# FPGA_Banks_64_65_HR.net
KiCad netlist of a schematic drawn in Altium Designer
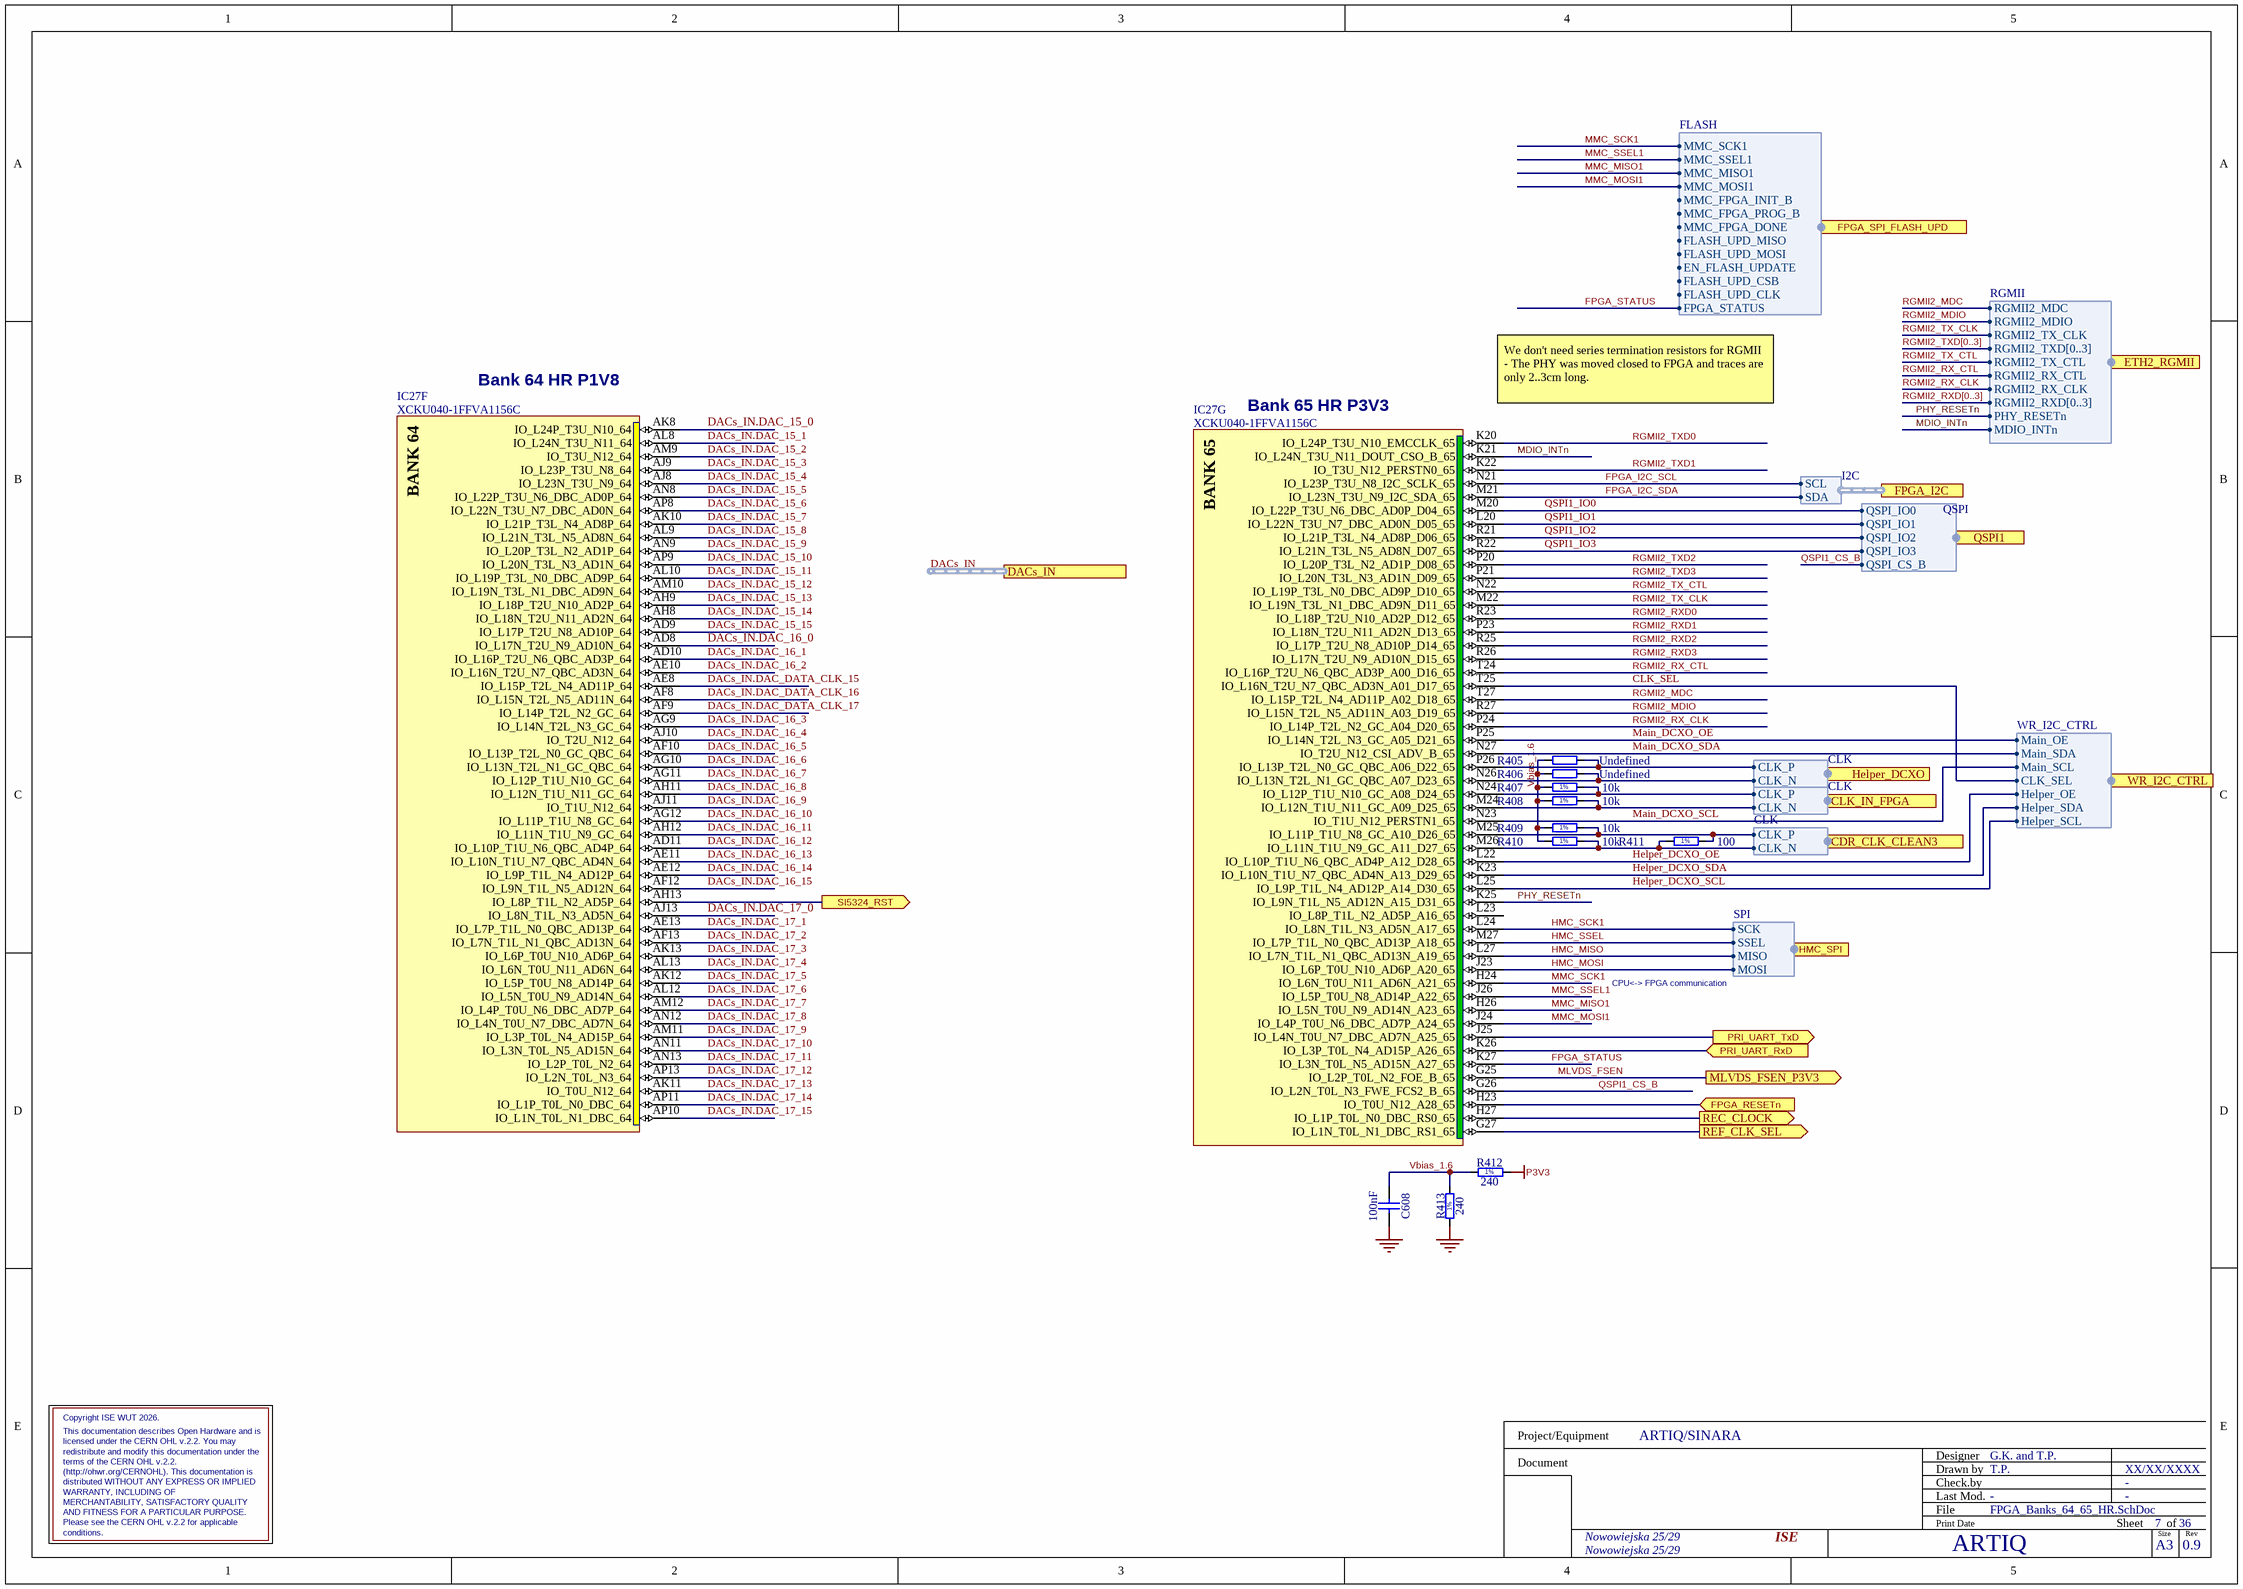
[diagram p0: FPGA_Banks_64_65_HR.SchDoc]

(export (version "E")
  (design (tool "Eeschema 10.0.6"))
  (components
    (comp (ref "C608")
      (value "100nF")
      (footprint "CAPC0603X33N")
      (description "Non-polarised capacitor")
      (fields
        (field (name "PART NUMBER") "CC0201_100NF_6.3V_10%_X5R")
        (field (name "VOLTAGE") "6.3V")
        (field (name "AUTHOR") "CERN DEM JLC")
      )
      (libsource (lib "Capacitors") (part "Capacitor - non polarized"))
    )
    (comp (ref "IC27")
      (value "XCKU040-1FFVA1156C")
      (footprint "BGA1156C100P34X34_3500X3500X350")
      (description "Kintex UltraScale FPGA, 520 I/O, 530K Cells, 1156-Ball BGA, Speed Grade 1, Commercial Grade")
      (fields (field (name "MANUFACTURER") "XILINX") (field (name "AUTHOR") "CERN DEM CA"))
      (libsource (lib "ICs And Semiconductors") (part "XCKU040-1FFVA1156C"))
    )
    (comp (ref "R405")
      (value "Undefined")
      (footprint "RESC1005X40N")
      (description "Resistor")
      (fields (field (name "PART NUMBER") "R0402_NO-VALUE") (field (name "AUTHOR") "CERN DEM JLC"))
      (libsource (lib "Resistors") (part "Resistor"))
    )
    (comp (ref "R406")
      (value "Undefined")
      (footprint "RESC1005X40N")
      (description "Resistor")
      (fields (field (name "PART NUMBER") "R0402_NO-VALUE") (field (name "AUTHOR") "CERN DEM JLC"))
      (libsource (lib "Resistors") (part "Resistor"))
    )
    (comp (ref "R407")
      (value "10k")
      (footprint "RESC1005X40N")
      (description "Resistor - 1%")
      (fields
        (field (name "PART NUMBER") "R0402_10K_1%_0.0625W_100PPM")
        (field (name "POWER") "0.0625W")
        (field (name "AUTHOR") "CERN DEM JLC")
      )
      (libsource (lib "Resistors") (part "Resistor - 1%"))
    )
    (comp (ref "R408")
      (value "10k")
      (footprint "RESC1005X40N")
      (description "Resistor - 1%")
      (fields
        (field (name "PART NUMBER") "R0402_10K_1%_0.0625W_100PPM")
        (field (name "POWER") "0.0625W")
        (field (name "AUTHOR") "CERN DEM JLC")
      )
      (libsource (lib "Resistors") (part "Resistor - 1%"))
    )
    (comp (ref "R409")
      (value "10k")
      (footprint "RESC1005X40N")
      (description "Resistor - 1%")
      (fields
        (field (name "PART NUMBER") "R0402_10K_1%_0.0625W_100PPM")
        (field (name "POWER") "0.0625W")
        (field (name "AUTHOR") "CERN DEM JLC")
      )
      (libsource (lib "Resistors") (part "Resistor - 1%"))
    )
    (comp (ref "R410")
      (value "10k")
      (footprint "RESC1005X40N")
      (description "Resistor - 1%")
      (fields
        (field (name "PART NUMBER") "R0402_10K_1%_0.0625W_100PPM")
        (field (name "POWER") "0.0625W")
        (field (name "AUTHOR") "CERN DEM JLC")
      )
      (libsource (lib "Resistors") (part "Resistor - 1%"))
    )
    (comp (ref "R411")
      (value "100")
      (footprint "RESC1005X40N")
      (description "Resistor - 1%")
      (fields
        (field (name "PART NUMBER") "R0402_100R_1%_0.0625W_100PPM")
        (field (name "POWER") "0.0625W")
        (field (name "AUTHOR") "CERN DEM JLC")
      )
      (libsource (lib "Resistors") (part "Resistor - 1%"))
    )
    (comp (ref "R412")
      (value "240")
      (footprint "RESC1005X40N")
      (description "Resistor - 1%")
      (fields
        (field (name "PART NUMBER") "R0402_240R_1%_0.0625W_100PPM")
        (field (name "POWER") "0.0625W")
        (field (name "AUTHOR") "CERN DEM JLC")
      )
      (libsource (lib "Resistors") (part "Resistor - 1%"))
    )
    (comp (ref "R413")
      (value "240")
      (footprint "RESC1005X40N")
      (description "Resistor - 1%")
      (fields
        (field (name "PART NUMBER") "R0402_240R_1%_0.0625W_100PPM")
        (field (name "POWER") "0.0625W")
        (field (name "AUTHOR") "CERN DEM JLC")
      )
      (libsource (lib "Resistors") (part "Resistor - 1%"))
    )
  )
  (nets
    (net (code "10") (name "/CLK_SEL") (class "Default")
      (node (ref "IC27") (pin "T25") (pinfunction "IO_L16N_T2U_N7_QBC_AD3N_A01_D17_65_T25") (pintype "bidirectional"))
    )
    (net (code "11") (name "/DACs_IN.DAC_15_0") (class "Default")
      (node (ref "IC27") (pin "AK8") (pinfunction "IO_L24P_T3U_N10_64_AK8") (pintype "bidirectional"))
    )
    (net (code "12") (name "/DACs_IN.DAC_15_1") (class "Default")
      (node (ref "IC27") (pin "AL8") (pinfunction "IO_L24N_T3U_N11_64_AL8") (pintype "bidirectional"))
    )
    (net (code "13") (name "/DACs_IN.DAC_15_2") (class "Default")
      (node (ref "IC27") (pin "AM9") (pinfunction "IO_T3U_N12_64_AM9") (pintype "bidirectional"))
    )
    (net (code "14") (name "/DACs_IN.DAC_15_3") (class "Default")
      (node (ref "IC27") (pin "AJ9") (pinfunction "IO_L23P_T3U_N8_64_AJ9") (pintype "bidirectional"))
    )
    (net (code "15") (name "/DACs_IN.DAC_15_4") (class "Default")
      (node (ref "IC27") (pin "AJ8") (pinfunction "IO_L23N_T3U_N9_64_AJ8") (pintype "bidirectional"))
    )
    (net (code "16") (name "/DACs_IN.DAC_15_5") (class "Default")
      (node (ref "IC27") (pin "AN8") (pinfunction "IO_L22P_T3U_N6_DBC_AD0P_64_AN8") (pintype "bidirectional"))
    )
    (net (code "17") (name "/DACs_IN.DAC_15_6") (class "Default")
      (node (ref "IC27") (pin "AP8") (pinfunction "IO_L22N_T3U_N7_DBC_AD0N_64_AP8") (pintype "bidirectional"))
    )
    (net (code "18") (name "/DACs_IN.DAC_15_7") (class "Default")
      (node (ref "IC27") (pin "AK10") (pinfunction "IO_L21P_T3L_N4_AD8P_64_AK10") (pintype "bidirectional"))
    )
    (net (code "19") (name "/DACs_IN.DAC_15_8") (class "Default")
      (node (ref "IC27") (pin "AL9") (pinfunction "IO_L21N_T3L_N5_AD8N_64_AL9") (pintype "bidirectional"))
    )
    (net (code "20") (name "/DACs_IN.DAC_15_9") (class "Default")
      (node (ref "IC27") (pin "AN9") (pinfunction "IO_L20P_T3L_N2_AD1P_64_AN9") (pintype "bidirectional"))
    )
    (net (code "21") (name "/DACs_IN.DAC_15_10") (class "Default")
      (node (ref "IC27") (pin "AP9") (pinfunction "IO_L20N_T3L_N3_AD1N_64_AP9") (pintype "bidirectional"))
    )
    (net (code "22") (name "/DACs_IN.DAC_15_11") (class "Default")
      (node (ref "IC27") (pin "AL10") (pinfunction "IO_L19P_T3L_N0_DBC_AD9P_64_AL10") (pintype "bidirectional"))
    )
    (net (code "23") (name "/DACs_IN.DAC_15_12") (class "Default")
      (node (ref "IC27") (pin "AM10") (pinfunction "IO_L19N_T3L_N1_DBC_AD9N_64_AM10") (pintype "bidirectional"))
    )
    (net (code "24") (name "/DACs_IN.DAC_15_13") (class "Default")
      (node (ref "IC27") (pin "AH9") (pinfunction "IO_L18P_T2U_N10_AD2P_64_AH9") (pintype "bidirectional"))
    )
    (net (code "25") (name "/DACs_IN.DAC_15_14") (class "Default")
      (node (ref "IC27") (pin "AH8") (pinfunction "IO_L18N_T2U_N11_AD2N_64_AH8") (pintype "bidirectional"))
    )
    (net (code "26") (name "/DACs_IN.DAC_15_15") (class "Default")
      (node (ref "IC27") (pin "AD9") (pinfunction "IO_L17P_T2U_N8_AD10P_64_AD9") (pintype "bidirectional"))
    )
    (net (code "27") (name "/DACs_IN.DAC_16_0") (class "Default")
      (node (ref "IC27") (pin "AD8") (pinfunction "IO_L17N_T2U_N9_AD10N_64_AD8") (pintype "bidirectional"))
    )
    (net (code "28") (name "/DACs_IN.DAC_16_1") (class "Default")
      (node (ref "IC27") (pin "AD10") (pinfunction "IO_L16P_T2U_N6_QBC_AD3P_64_AD10") (pintype "bidirectional"))
    )
    (net (code "29") (name "/DACs_IN.DAC_16_2") (class "Default")
      (node (ref "IC27") (pin "AE10") (pinfunction "IO_L16N_T2U_N7_QBC_AD3N_64_AE10") (pintype "bidirectional"))
    )
    (net (code "30") (name "/DACs_IN.DAC_16_3") (class "Default")
      (node (ref "IC27") (pin "AG9") (pinfunction "IO_L14N_T2L_N3_GC_64_AG9") (pintype "bidirectional"))
    )
    (net (code "31") (name "/DACs_IN.DAC_16_4") (class "Default")
      (node (ref "IC27") (pin "AJ10") (pinfunction "IO_T2U_N12_64_AJ10") (pintype "bidirectional"))
    )
    (net (code "32") (name "/DACs_IN.DAC_16_5") (class "Default")
      (node (ref "IC27") (pin "AF10") (pinfunction "IO_L13P_T2L_N0_GC_QBC_64_AF10") (pintype "bidirectional"))
    )
    (net (code "33") (name "/DACs_IN.DAC_16_6") (class "Default")
      (node (ref "IC27") (pin "AG10") (pinfunction "IO_L13N_T2L_N1_GC_QBC_64_AG10") (pintype "bidirectional"))
    )
    (net (code "34") (name "/DACs_IN.DAC_16_7") (class "Default")
      (node (ref "IC27") (pin "AG11") (pinfunction "IO_L12P_T1U_N10_GC_64_AG11") (pintype "bidirectional"))
    )
    (net (code "35") (name "/DACs_IN.DAC_16_8") (class "Default")
      (node (ref "IC27") (pin "AH11") (pinfunction "IO_L12N_T1U_N11_GC_64_AH11") (pintype "bidirectional"))
    )
    (net (code "36") (name "/DACs_IN.DAC_16_9") (class "Default")
      (node (ref "IC27") (pin "AJ11") (pinfunction "IO_T1U_N12_64_AJ11") (pintype "bidirectional"))
    )
    (net (code "37") (name "/DACs_IN.DAC_16_10") (class "Default")
      (node (ref "IC27") (pin "AG12") (pinfunction "IO_L11P_T1U_N8_GC_64_AG12") (pintype "bidirectional"))
    )
    (net (code "38") (name "/DACs_IN.DAC_16_11") (class "Default")
      (node (ref "IC27") (pin "AH12") (pinfunction "IO_L11N_T1U_N9_GC_64_AH12") (pintype "bidirectional"))
    )
    (net (code "39") (name "/DACs_IN.DAC_16_12") (class "Default")
      (node (ref "IC27") (pin "AD11") (pinfunction "IO_L10P_T1U_N6_QBC_AD4P_64_AD11") (pintype "bidirectional"))
    )
    (net (code "40") (name "/DACs_IN.DAC_16_13") (class "Default")
      (node (ref "IC27") (pin "AE11") (pinfunction "IO_L10N_T1U_N7_QBC_AD4N_64_AE11") (pintype "bidirectional"))
    )
    (net (code "41") (name "/DACs_IN.DAC_16_14") (class "Default")
      (node (ref "IC27") (pin "AE12") (pinfunction "IO_L9P_T1L_N4_AD12P_64_AE12") (pintype "bidirectional"))
    )
    (net (code "42") (name "/DACs_IN.DAC_16_15") (class "Default")
      (node (ref "IC27") (pin "AF12") (pinfunction "IO_L9N_T1L_N5_AD12N_64_AF12") (pintype "bidirectional"))
    )
    (net (code "43") (name "/DACs_IN.DAC_17_0") (class "Default")
      (node (ref "IC27") (pin "AJ13") (pinfunction "IO_L8N_T1L_N3_AD5N_64_AJ13") (pintype "bidirectional"))
    )
    (net (code "44") (name "/DACs_IN.DAC_17_1") (class "Default")
      (node (ref "IC27") (pin "AE13") (pinfunction "IO_L7P_T1L_N0_QBC_AD13P_64_AE13") (pintype "bidirectional"))
    )
    (net (code "45") (name "/DACs_IN.DAC_17_2") (class "Default")
      (node (ref "IC27") (pin "AF13") (pinfunction "IO_L7N_T1L_N1_QBC_AD13N_64_AF13") (pintype "bidirectional"))
    )
    (net (code "46") (name "/DACs_IN.DAC_17_3") (class "Default")
      (node (ref "IC27") (pin "AK13") (pinfunction "IO_L6P_T0U_N10_AD6P_64_AK13") (pintype "bidirectional"))
    )
    (net (code "47") (name "/DACs_IN.DAC_17_4") (class "Default")
      (node (ref "IC27") (pin "AL13") (pinfunction "IO_L6N_T0U_N11_AD6N_64_AL13") (pintype "bidirectional"))
    )
    (net (code "48") (name "/DACs_IN.DAC_17_5") (class "Default")
      (node (ref "IC27") (pin "AK12") (pinfunction "IO_L5P_T0U_N8_AD14P_64_AK12") (pintype "bidirectional"))
    )
    (net (code "49") (name "/DACs_IN.DAC_17_6") (class "Default")
      (node (ref "IC27") (pin "AL12") (pinfunction "IO_L5N_T0U_N9_AD14N_64_AL12") (pintype "bidirectional"))
    )
    (net (code "50") (name "/DACs_IN.DAC_17_7") (class "Default")
      (node (ref "IC27") (pin "AM12") (pinfunction "IO_L4P_T0U_N6_DBC_AD7P_64_AM12") (pintype "bidirectional"))
    )
    (net (code "51") (name "/DACs_IN.DAC_17_8") (class "Default")
      (node (ref "IC27") (pin "AN12") (pinfunction "IO_L4N_T0U_N7_DBC_AD7N_64_AN12") (pintype "bidirectional"))
    )
    (net (code "52") (name "/DACs_IN.DAC_17_9") (class "Default")
      (node (ref "IC27") (pin "AM11") (pinfunction "IO_L3P_T0L_N4_AD15P_64_AM11") (pintype "bidirectional"))
    )
    (net (code "53") (name "/DACs_IN.DAC_17_10") (class "Default")
      (node (ref "IC27") (pin "AN11") (pinfunction "IO_L3N_T0L_N5_AD15N_64_AN11") (pintype "bidirectional"))
    )
    (net (code "54") (name "/DACs_IN.DAC_17_11") (class "Default")
      (node (ref "IC27") (pin "AN13") (pinfunction "IO_L2P_T0L_N2_64_AN13") (pintype "bidirectional"))
    )
    (net (code "55") (name "/DACs_IN.DAC_17_12") (class "Default")
      (node (ref "IC27") (pin "AP13") (pinfunction "IO_L2N_T0L_N3_64_AP13") (pintype "bidirectional"))
    )
    (net (code "56") (name "/DACs_IN.DAC_17_13") (class "Default")
      (node (ref "IC27") (pin "AK11") (pinfunction "IO_T0U_N12_64_AK11") (pintype "bidirectional"))
    )
    (net (code "57") (name "/DACs_IN.DAC_17_14") (class "Default")
      (node (ref "IC27") (pin "AP11") (pinfunction "IO_L1P_T0L_N0_DBC_64_AP11") (pintype "bidirectional"))
    )
    (net (code "58") (name "/DACs_IN.DAC_17_15") (class "Default")
      (node (ref "IC27") (pin "AP10") (pinfunction "IO_L1N_T0L_N1_DBC_64_AP10") (pintype "bidirectional"))
    )
    (net (code "59") (name "/DACs_IN.DAC_DATA_CLK_15") (class "Default")
      (node (ref "IC27") (pin "AE8") (pinfunction "IO_L15P_T2L_N4_AD11P_64_AE8") (pintype "bidirectional"))
    )
    (net (code "60") (name "/DACs_IN.DAC_DATA_CLK_16") (class "Default")
      (node (ref "IC27") (pin "AF8") (pinfunction "IO_L15N_T2L_N5_AD11N_64_AF8") (pintype "bidirectional"))
    )
    (net (code "61") (name "/DACs_IN.DAC_DATA_CLK_17") (class "Default")
      (node (ref "IC27") (pin "AF9") (pinfunction "IO_L14P_T2L_N2_GC_64_AF9") (pintype "bidirectional"))
    )
    (net (code "63") (name "/FPGA_I2C_SCL") (class "Default")
      (node (ref "IC27") (pin "N21") (pinfunction "IO_L23P_T3U_N8_I2C_SCLK_65_N21") (pintype "bidirectional"))
    )
    (net (code "64") (name "/FPGA_I2C_SDA") (class "Default")
      (node (ref "IC27") (pin "M21") (pinfunction "IO_L23N_T3U_N9_I2C_SDA_65_M21") (pintype "bidirectional"))
    )
    (net (code "65") (name "/FPGA_RESETn") (class "Default")
      (node (ref "IC27") (pin "H23") (pinfunction "IO_T0U_N12_A28_65_H23") (pintype "bidirectional"))
    )
    (net (code "66") (name "/FPGA_STATUS") (class "Default")
      (node (ref "IC27") (pin "K27") (pinfunction "IO_L3N_T0L_N5_AD15N_A27_65_K27") (pintype "bidirectional"))
    )
    (net (code "67") (name "/HMC_MISO") (class "Default")
      (node (ref "IC27") (pin "L27") (pinfunction "IO_L7N_T1L_N1_QBC_AD13N_A19_65_L27") (pintype "bidirectional"))
    )
    (net (code "68") (name "/HMC_MOSI") (class "Default")
      (node (ref "IC27") (pin "J23") (pinfunction "IO_L6P_T0U_N10_AD6P_A20_65_J23") (pintype "bidirectional"))
    )
    (net (code "69") (name "/HMC_SCK1") (class "Default")
      (node (ref "IC27") (pin "L24") (pinfunction "IO_L8N_T1L_N3_AD5N_A17_65_L24") (pintype "bidirectional"))
    )
    (net (code "70") (name "/HMC_SSEL") (class "Default")
      (node (ref "IC27") (pin "M27") (pinfunction "IO_L7P_T1L_N0_QBC_AD13P_A18_65_M27") (pintype "bidirectional"))
    )
    (net (code "71") (name "/Helper_DCXO_OE") (class "Default")
      (node (ref "IC27") (pin "L22") (pinfunction "IO_L10P_T1U_N6_QBC_AD4P_A12_D28_65_L22") (pintype "bidirectional"))
    )
    (net (code "72") (name "/Helper_DCXO_SCL") (class "Default")
      (node (ref "IC27") (pin "L25") (pinfunction "IO_L9P_T1L_N4_AD12P_A14_D30_65_L25") (pintype "bidirectional"))
    )
    (net (code "73") (name "/Helper_DCXO_SDA") (class "Default")
      (node (ref "IC27") (pin "K23") (pinfunction "IO_L10N_T1U_N7_QBC_AD4N_A13_D29_65_K23") (pintype "bidirectional"))
    )
    (net (code "75") (name "/MDIO_INTn") (class "Default")
      (node (ref "IC27") (pin "K21") (pinfunction "IO_L24N_T3U_N11_DOUT_CSO_B_65_K21") (pintype "bidirectional"))
    )
    (net (code "76") (name "/MLVDS_FSEN") (class "Default")
      (node (ref "IC27") (pin "G25") (pinfunction "IO_L2P_T0L_N2_FOE_B_65_G25") (pintype "bidirectional"))
    )
    (net (code "77") (name "/MMC_MISO1") (class "Default")
      (node (ref "IC27") (pin "H26") (pinfunction "IO_L5N_T0U_N9_AD14N_A23_65_H26") (pintype "bidirectional"))
    )
    (net (code "78") (name "/MMC_MOSI1") (class "Default")
      (node (ref "IC27") (pin "J24") (pinfunction "IO_L4P_T0U_N6_DBC_AD7P_A24_65_J24") (pintype "bidirectional"))
    )
    (net (code "79") (name "/MMC_SCK1") (class "Default")
      (node (ref "IC27") (pin "H24") (pinfunction "IO_L6N_T0U_N11_AD6N_A21_65_H24") (pintype "bidirectional"))
    )
    (net (code "80") (name "/MMC_SSEL1") (class "Default")
      (node (ref "IC27") (pin "J26") (pinfunction "IO_L5P_T0U_N8_AD14P_A22_65_J26") (pintype "bidirectional"))
    )
    (net (code "81") (name "/Main_DCXO_OE") (class "Default")
      (node (ref "IC27") (pin "P25") (pinfunction "IO_L14N_T2L_N3_GC_A05_D21_65_P25") (pintype "bidirectional"))
    )
    (net (code "82") (name "/Main_DCXO_SCL") (class "Default")
      (node (ref "IC27") (pin "N23") (pinfunction "IO_T1U_N12_PERSTN1_65_N23") (pintype "bidirectional"))
    )
    (net (code "83") (name "/Main_DCXO_SDA") (class "Default")
      (node (ref "IC27") (pin "N27") (pinfunction "IO_T2U_N12_CSI_ADV_B_65_N27") (pintype "bidirectional"))
    )
    (net (code "84") (name "/PHY_RESETn") (class "Default")
      (node (ref "IC27") (pin "K25") (pinfunction "IO_L9N_T1L_N5_AD12N_A15_D31_65_K25") (pintype "bidirectional"))
    )
    (net (code "85") (name "/PRI_UART_RxD") (class "Default")
      (node (ref "IC27") (pin "K26") (pinfunction "IO_L3P_T0L_N4_AD15P_A26_65_K26") (pintype "bidirectional"))
    )
    (net (code "86") (name "/PRI_UART_TxD") (class "Default")
      (node (ref "IC27") (pin "J25") (pinfunction "IO_L4N_T0U_N7_DBC_AD7N_A25_65_J25") (pintype "bidirectional"))
    )
    (net (code "87") (name "/QSPI1_CS_B") (class "Default")
      (node (ref "IC27") (pin "G26") (pinfunction "IO_L2N_T0L_N3_FWE_FCS2_B_65_G26") (pintype "bidirectional"))
    )
    (net (code "88") (name "/QSPI1_IO0") (class "Default")
      (node (ref "IC27") (pin "M20") (pinfunction "IO_L22P_T3U_N6_DBC_AD0P_D04_65_M20") (pintype "bidirectional"))
    )
    (net (code "89") (name "/QSPI1_IO1") (class "Default")
      (node (ref "IC27") (pin "L20") (pinfunction "IO_L22N_T3U_N7_DBC_AD0N_D05_65_L20") (pintype "bidirectional"))
    )
    (net (code "90") (name "/QSPI1_IO2") (class "Default")
      (node (ref "IC27") (pin "R21") (pinfunction "IO_L21P_T3L_N4_AD8P_D06_65_R21") (pintype "bidirectional"))
    )
    (net (code "91") (name "/QSPI1_IO3") (class "Default")
      (node (ref "IC27") (pin "R22") (pinfunction "IO_L21N_T3L_N5_AD8N_D07_65_R22") (pintype "bidirectional"))
    )
    (net (code "92") (name "/REC_CLOCK") (class "Default")
      (node (ref "IC27") (pin "H27") (pinfunction "IO_L1P_T0L_N0_DBC_RS0_65_H27") (pintype "bidirectional"))
    )
    (net (code "93") (name "/REF_CLK_SEL") (class "Default")
      (node (ref "IC27") (pin "G27") (pinfunction "IO_L1N_T0L_N1_DBC_RS1_65_G27") (pintype "bidirectional"))
    )
    (net (code "94") (name "/RGMII2_MDC") (class "Default")
      (node (ref "IC27") (pin "T27") (pinfunction "IO_L15P_T2L_N4_AD11P_A02_D18_65_T27") (pintype "bidirectional"))
    )
    (net (code "95") (name "/RGMII2_MDIO") (class "Default")
      (node (ref "IC27") (pin "R27") (pinfunction "IO_L15N_T2L_N5_AD11N_A03_D19_65_R27") (pintype "bidirectional"))
    )
    (net (code "96") (name "/RGMII2_RXD0") (class "Default")
      (node (ref "IC27") (pin "R23") (pinfunction "IO_L18P_T2U_N10_AD2P_D12_65_R23") (pintype "bidirectional"))
    )
    (net (code "97") (name "/RGMII2_RXD1") (class "Default")
      (node (ref "IC27") (pin "P23") (pinfunction "IO_L18N_T2U_N11_AD2N_D13_65_P23") (pintype "bidirectional"))
    )
    (net (code "98") (name "/RGMII2_RXD2") (class "Default")
      (node (ref "IC27") (pin "R25") (pinfunction "IO_L17P_T2U_N8_AD10P_D14_65_R25") (pintype "bidirectional"))
    )
    (net (code "99") (name "/RGMII2_RXD3") (class "Default")
      (node (ref "IC27") (pin "R26") (pinfunction "IO_L17N_T2U_N9_AD10N_D15_65_R26") (pintype "bidirectional"))
    )
    (net (code "101") (name "/RGMII2_RX_CLK") (class "Default")
      (node (ref "IC27") (pin "P24") (pinfunction "IO_L14P_T2L_N2_GC_A04_D20_65_P24") (pintype "bidirectional"))
    )
    (net (code "102") (name "/RGMII2_RX_CTL") (class "Default")
      (node (ref "IC27") (pin "T24") (pinfunction "IO_L16P_T2U_N6_QBC_AD3P_A00_D16_65_T24") (pintype "bidirectional"))
    )
    (net (code "103") (name "/RGMII2_TXD0") (class "Default")
      (node (ref "IC27") (pin "K20") (pinfunction "IO_L24P_T3U_N10_EMCCLK_65_K20") (pintype "bidirectional"))
    )
    (net (code "104") (name "/RGMII2_TXD1") (class "Default")
      (node (ref "IC27") (pin "K22") (pinfunction "IO_T3U_N12_PERSTN0_65_K22") (pintype "bidirectional"))
    )
    (net (code "105") (name "/RGMII2_TXD2") (class "Default")
      (node (ref "IC27") (pin "P20") (pinfunction "IO_L20P_T3L_N2_AD1P_D08_65_P20") (pintype "bidirectional"))
    )
    (net (code "106") (name "/RGMII2_TXD3") (class "Default")
      (node (ref "IC27") (pin "P21") (pinfunction "IO_L20N_T3L_N3_AD1N_D09_65_P21") (pintype "bidirectional"))
    )
    (net (code "107") (name "/RGMII2_TX_CLK") (class "Default")
      (node (ref "IC27") (pin "M22") (pinfunction "IO_L19N_T3L_N1_DBC_AD9N_D11_65_M22") (pintype "bidirectional"))
    )
    (net (code "108") (name "/RGMII2_TX_CTL") (class "Default")
      (node (ref "IC27") (pin "N22") (pinfunction "IO_L19P_T3L_N0_DBC_AD9P_D10_65_N22") (pintype "bidirectional"))
    )
    (net (code "109") (name "/SI5324_RST") (class "Default")
      (node (ref "IC27") (pin "AH13") (pinfunction "IO_L8P_T1L_N2_AD5P_64_AH13") (pintype "bidirectional"))
    )
    (net (code "110") (name "/Vbias_1.6") (class "Default")
      (node (ref "C608") (pin "1") (pinfunction "1_1") (pintype "passive"))
      (node (ref "R405") (pin "1") (pinfunction "1_1") (pintype "passive"))
      (node (ref "R406") (pin "1") (pinfunction "1_1") (pintype "passive"))
      (node (ref "R407") (pin "1") (pinfunction "1_1") (pintype "passive"))
      (node (ref "R408") (pin "1") (pinfunction "1_1") (pintype "passive"))
      (node (ref "R409") (pin "1") (pinfunction "1_1") (pintype "passive"))
      (node (ref "R410") (pin "1") (pinfunction "1_1") (pintype "passive"))
      (node (ref "R412") (pin "1") (pinfunction "1_1") (pintype "passive"))
      (node (ref "R413") (pin "2") (pinfunction "2_2") (pintype "passive"))
    )
    (net (code "119") (name "GND") (class "Default")
      (node (ref "C608") (pin "2") (pinfunction "2_2") (pintype "passive"))
      (node (ref "R413") (pin "1") (pinfunction "1_1") (pintype "passive"))
    )
    (net (code "120") (name "Net-(IC27G-IO_L11N_T1U_N9_GC_A11_D27_65)") (class "Default")
      (node (ref "IC27") (pin "M26") (pinfunction "IO_L11N_T1U_N9_GC_A11_D27_65_M26") (pintype "bidirectional"))
      (node (ref "R410") (pin "2") (pinfunction "2_2") (pintype "passive"))
      (node (ref "R411") (pin "1") (pinfunction "1_1") (pintype "passive"))
    )
    (net (code "121") (name "Net-(IC27G-IO_L11P_T1U_N8_GC_A10_D26_65)") (class "Default")
      (node (ref "IC27") (pin "M25") (pinfunction "IO_L11P_T1U_N8_GC_A10_D26_65_M25") (pintype "bidirectional"))
      (node (ref "R409") (pin "2") (pinfunction "2_2") (pintype "passive"))
      (node (ref "R411") (pin "2") (pinfunction "2_2") (pintype "passive"))
    )
    (net (code "122") (name "Net-(IC27G-IO_L12N_T1U_N11_GC_A09_D25_65)") (class "Default")
      (node (ref "IC27") (pin "M24") (pinfunction "IO_L12N_T1U_N11_GC_A09_D25_65_M24") (pintype "bidirectional"))
      (node (ref "R408") (pin "2") (pinfunction "2_2") (pintype "passive"))
    )
    (net (code "123") (name "Net-(IC27G-IO_L12P_T1U_N10_GC_A08_D24_65)") (class "Default")
      (node (ref "IC27") (pin "N24") (pinfunction "IO_L12P_T1U_N10_GC_A08_D24_65_N24") (pintype "bidirectional"))
      (node (ref "R407") (pin "2") (pinfunction "2_2") (pintype "passive"))
    )
    (net (code "124") (name "Net-(IC27G-IO_L13N_T2L_N1_GC_QBC_A07_D23_65)") (class "Default")
      (node (ref "IC27") (pin "N26") (pinfunction "IO_L13N_T2L_N1_GC_QBC_A07_D23_65_N26") (pintype "bidirectional"))
      (node (ref "R406") (pin "2") (pinfunction "2_2") (pintype "passive"))
    )
    (net (code "125") (name "Net-(IC27G-IO_L13P_T2L_N0_GC_QBC_A06_D22_65)") (class "Default")
      (node (ref "IC27") (pin "P26") (pinfunction "IO_L13P_T2L_N0_GC_QBC_A06_D22_65_P26") (pintype "bidirectional"))
      (node (ref "R405") (pin "2") (pinfunction "2_2") (pintype "passive"))
    )
    (net (code "126") (name "P3V3") (class "Default")
      (node (ref "R412") (pin "2") (pinfunction "2_2") (pintype "passive"))
    )
    (net (code "127") (name "unconnected-(IC27G-IO_L8P_T1L_N2_AD5P_A16_65-PadL23)") (class "Default")
      (node (ref "IC27") (pin "L23") (pinfunction "IO_L8P_T1L_N2_AD5P_A16_65_L23") (pintype "bidirectional"))
    )
  )
)
